# F387_Mini_Dev.net
KiCad netlist of a schematic drawn in EAGLE
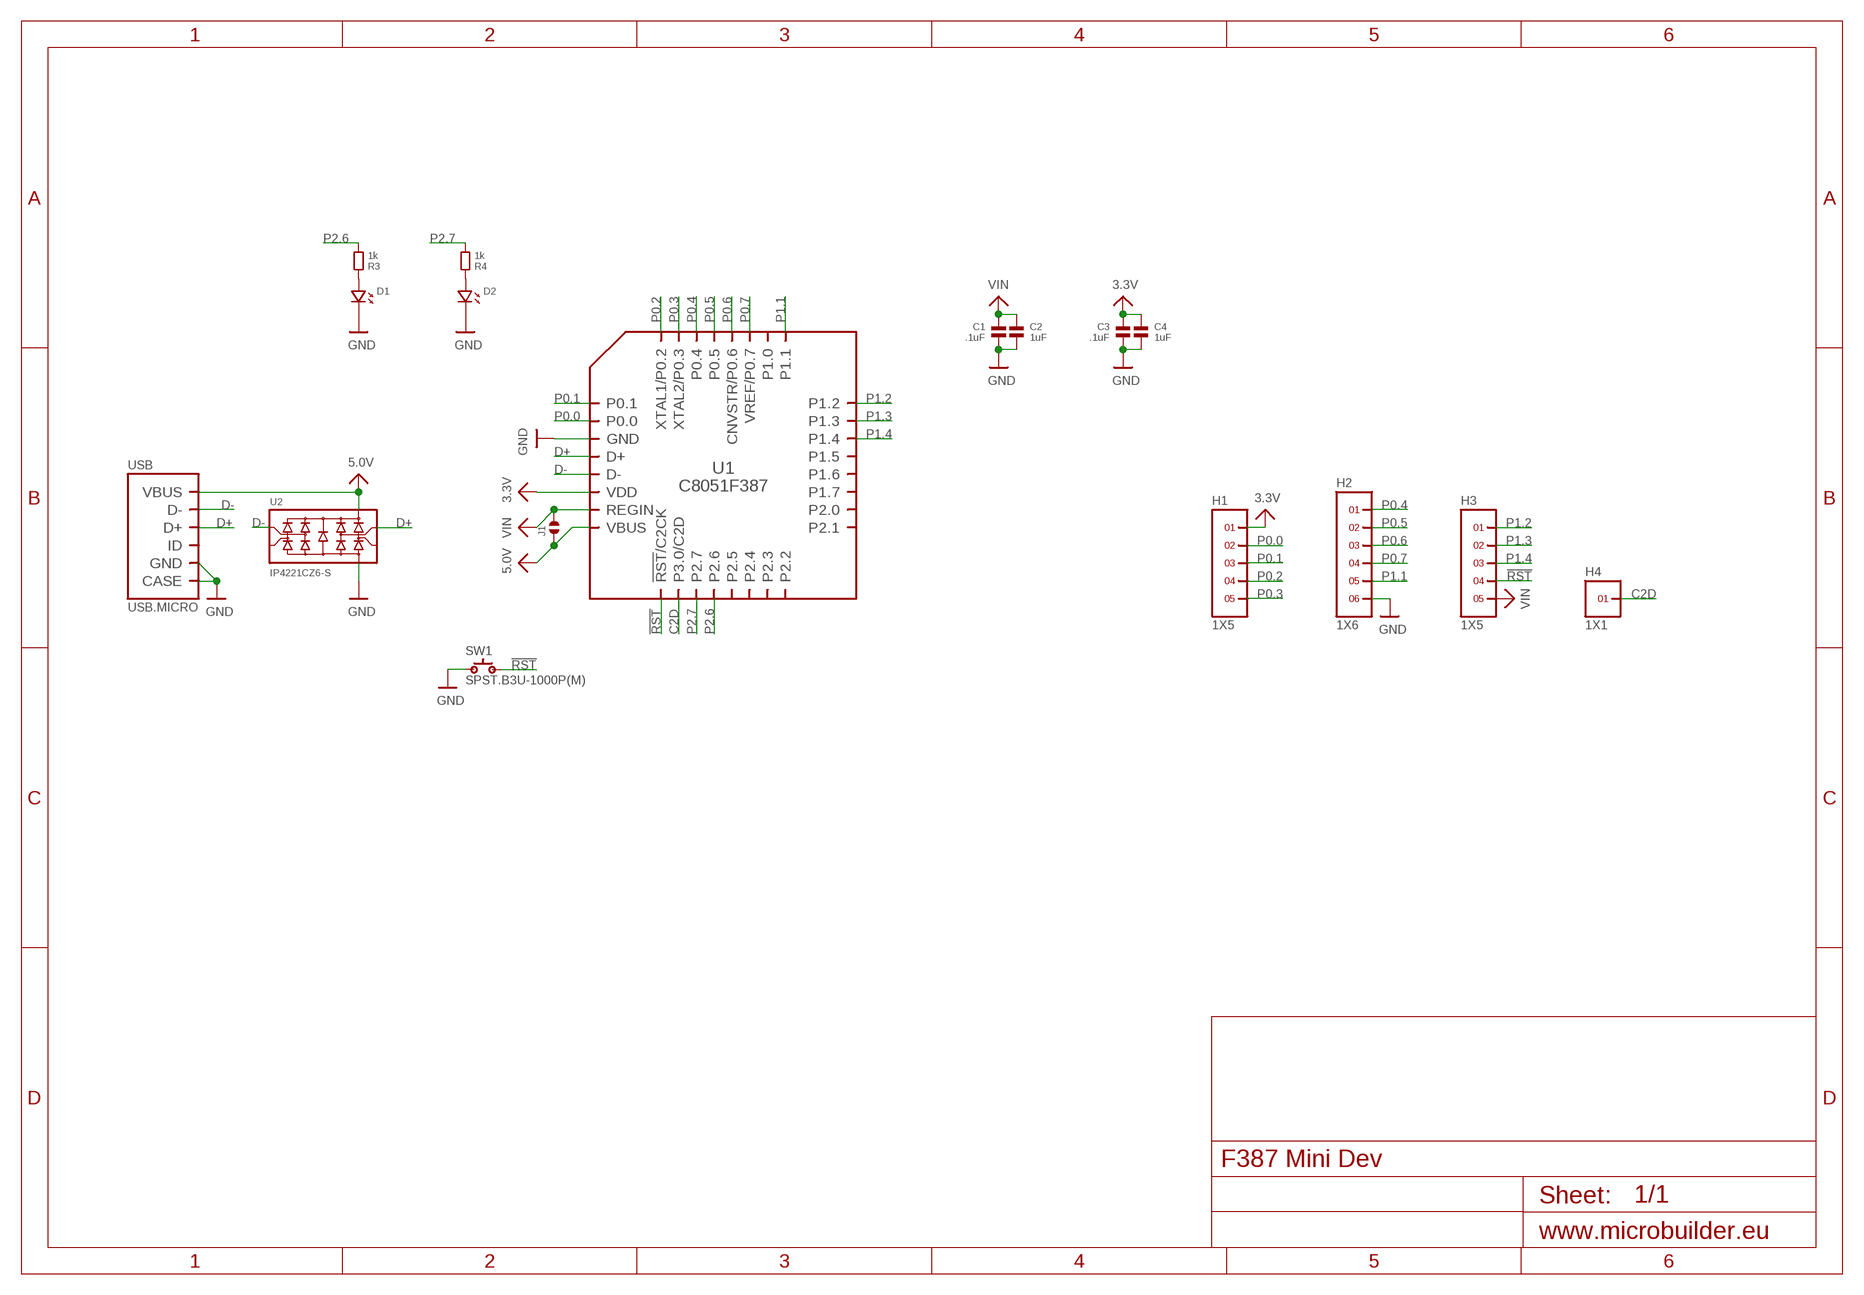
[diagram p0: schematic, sheet 1]

(export (version "E")
  (design (tool "Eeschema 10.0.6"))
  (components
    (comp (ref "C1")
      (value ".1uF")
      (footprint "eagle-import:0402")
      (libsource (lib "eagle-import") (part "CAPACITOR.0402"))
    )
    (comp (ref "C2")
      (value "1uF")
      (footprint "eagle-import:0402")
      (libsource (lib "eagle-import") (part "CAPACITOR.0402"))
    )
    (comp (ref "C3")
      (value ".1uF")
      (footprint "eagle-import:0402")
      (libsource (lib "eagle-import") (part "CAPACITOR.0402"))
    )
    (comp (ref "C4")
      (value "1uF")
      (footprint "eagle-import:0402")
      (libsource (lib "eagle-import") (part "CAPACITOR.0402"))
    )
    (comp (ref "D1")
      (value "LED.0402")
      (footprint "eagle-import:0402.LED")
      (libsource (lib "eagle-import") (part "LED.0402"))
    )
    (comp (ref "D2")
      (value "LED.0402")
      (footprint "eagle-import:0402.LED")
      (libsource (lib "eagle-import") (part "LED.0402"))
    )
    (comp (ref "H1")
      (value "1X5")
      (footprint "eagle-import:1X5")
      (libsource (lib "eagle-import") (part "1X5"))
    )
    (comp (ref "H2")
      (value "1X6")
      (footprint "eagle-import:1X6")
      (libsource (lib "eagle-import") (part "1X6"))
    )
    (comp (ref "H3")
      (value "1X5")
      (footprint "eagle-import:1X5")
      (libsource (lib "eagle-import") (part "1X5"))
    )
    (comp (ref "H4")
      (value "1X1")
      (footprint "eagle-import:1X1")
      (libsource (lib "eagle-import") (part "1X1"))
    )
    (comp (ref "J1")
      (value "SOLDERJUMPER.2.SML")
      (footprint "eagle-import:2.SML")
      (libsource (lib "eagle-import") (part "SOLDERJUMPER.2.SML"))
    )
    (comp (ref "R3")
      (value "1k")
      (footprint "eagle-import:0402")
      (libsource (lib "eagle-import") (part "RESISTOR.0402"))
    )
    (comp (ref "R4")
      (value "1k")
      (footprint "eagle-import:0402")
      (libsource (lib "eagle-import") (part "RESISTOR.0402"))
    )
    (comp (ref "SW1")
      (value "SPST.B3U-1000P(M)")
      (footprint "eagle-import:B3U-1000P(M)")
      (libsource (lib "eagle-import") (part "SPST.B3U-1000P(M)"))
    )
    (comp (ref "U1")
      (value "C8051F387")
      (footprint "eagle-import:QFN32")
      (libsource (lib "eagle-import") (part "C8051F381/3/5/7.QFN"))
    )
    (comp (ref "U2")
      (value "IP4221CZ6-S")
      (footprint "eagle-import:DFN1410-6")
      (libsource (lib "eagle-import") (part "IP4221CZ6-S"))
    )
    (comp (ref "USB")
      (value "USB.MICRO")
      (footprint "eagle-import:1554266-1")
      (libsource (lib "eagle-import") (part "USB.MICRO"))
    )
  )
  (nets
    (net (code "1") (name "/C2D") (class "Default")
      (node (ref "H4") (pin "1") (pinfunction "1_1") (pintype "bidirectional"))
      (node (ref "U1") (pin "10") (pinfunction "P3.0/C2D_10") (pintype "bidirectional"))
    )
    (net (code "2") (name "/D+") (class "Default")
      (node (ref "U1") (pin "4") (pinfunction "D+_4") (pintype "bidirectional"))
      (node (ref "U2") (pin "3") (pinfunction "3_3") (pintype "bidirectional"))
      (node (ref "USB") (pin "3") (pinfunction "D+_3") (pintype "bidirectional"))
    )
    (net (code "3") (name "/D-") (class "Default")
      (node (ref "U1") (pin "5") (pinfunction "D-_5") (pintype "bidirectional"))
      (node (ref "U2") (pin "1") (pinfunction "1_1") (pintype "bidirectional"))
      (node (ref "USB") (pin "2") (pinfunction "D-_2") (pintype "bidirectional"))
    )
    (net (code "4") (name "/P0.0") (class "Default")
      (node (ref "H1") (pin "2") (pinfunction "2_2") (pintype "bidirectional"))
      (node (ref "U1") (pin "2") (pinfunction "P0.0_2") (pintype "bidirectional"))
    )
    (net (code "5") (name "/P0.1") (class "Default")
      (node (ref "H1") (pin "3") (pinfunction "3_3") (pintype "bidirectional"))
      (node (ref "U1") (pin "1") (pinfunction "P0.1_1") (pintype "bidirectional"))
    )
    (net (code "6") (name "/P0.2") (class "Default")
      (node (ref "H1") (pin "4") (pinfunction "4_4") (pintype "bidirectional"))
      (node (ref "U1") (pin "32") (pinfunction "XTAL1/P0.2_32") (pintype "bidirectional"))
    )
    (net (code "7") (name "/P0.3") (class "Default")
      (node (ref "H1") (pin "5") (pinfunction "5_5") (pintype "bidirectional"))
      (node (ref "U1") (pin "31") (pinfunction "XTAL2/P0.3_31") (pintype "bidirectional"))
    )
    (net (code "8") (name "/P0.4") (class "Default")
      (node (ref "H2") (pin "1") (pinfunction "1_1") (pintype "bidirectional"))
      (node (ref "U1") (pin "30") (pinfunction "P0.4_30") (pintype "bidirectional"))
    )
    (net (code "9") (name "/P0.5") (class "Default")
      (node (ref "H2") (pin "2") (pinfunction "2_2") (pintype "bidirectional"))
      (node (ref "U1") (pin "29") (pinfunction "P0.5_29") (pintype "bidirectional"))
    )
    (net (code "10") (name "/P0.6") (class "Default")
      (node (ref "H2") (pin "3") (pinfunction "3_3") (pintype "bidirectional"))
      (node (ref "U1") (pin "28") (pinfunction "CNVSTR/P0.6_28") (pintype "bidirectional"))
    )
    (net (code "11") (name "/P0.7") (class "Default")
      (node (ref "H2") (pin "4") (pinfunction "4_4") (pintype "bidirectional"))
      (node (ref "U1") (pin "27") (pinfunction "VREF/P0.7_27") (pintype "bidirectional"))
    )
    (net (code "12") (name "/P1.1") (class "Default")
      (node (ref "H2") (pin "5") (pinfunction "5_5") (pintype "bidirectional"))
      (node (ref "U1") (pin "25") (pinfunction "P1.1_25") (pintype "bidirectional"))
    )
    (net (code "13") (name "/P1.2") (class "Default")
      (node (ref "H3") (pin "1") (pinfunction "1_1") (pintype "bidirectional"))
      (node (ref "U1") (pin "24") (pinfunction "P1.2_24") (pintype "bidirectional"))
    )
    (net (code "14") (name "/P1.3") (class "Default")
      (node (ref "H3") (pin "2") (pinfunction "2_2") (pintype "bidirectional"))
      (node (ref "U1") (pin "23") (pinfunction "P1.3_23") (pintype "bidirectional"))
    )
    (net (code "15") (name "/P1.4") (class "Default")
      (node (ref "H3") (pin "3") (pinfunction "3_3") (pintype "bidirectional"))
      (node (ref "U1") (pin "22") (pinfunction "P1.4_22") (pintype "bidirectional"))
    )
    (net (code "16") (name "/P2.6") (class "Default")
      (node (ref "R3") (pin "2") (pinfunction "2_2") (pintype "bidirectional"))
      (node (ref "U1") (pin "12") (pinfunction "P2.6_12") (pintype "bidirectional"))
    )
    (net (code "17") (name "/P2.7") (class "Default")
      (node (ref "R4") (pin "2") (pinfunction "2_2") (pintype "bidirectional"))
      (node (ref "U1") (pin "11") (pinfunction "P2.7_11") (pintype "bidirectional"))
    )
    (net (code "18") (name "/~{RST}") (class "Default")
      (node (ref "H3") (pin "4") (pinfunction "4_4") (pintype "bidirectional"))
      (node (ref "SW1") (pin "2") (pinfunction "2_2") (pintype "bidirectional"))
      (node (ref "U1") (pin "9") (pinfunction "~{RST}/C2CK_9") (pintype "bidirectional"))
    )
    (net (code "19") (name "3.3V") (class "Default")
      (node (ref "C3") (pin "1") (pinfunction "1_1") (pintype "bidirectional"))
      (node (ref "C4") (pin "1") (pinfunction "1_1") (pintype "bidirectional"))
      (node (ref "H1") (pin "1") (pinfunction "1_1") (pintype "bidirectional"))
      (node (ref "U1") (pin "6") (pinfunction "VDD_6") (pintype "bidirectional"))
    )
    (net (code "20") (name "5.0V") (class "Default")
      (node (ref "J1") (pin "1") (pinfunction "1_1") (pintype "bidirectional"))
      (node (ref "U1") (pin "8") (pinfunction "VBUS_8") (pintype "bidirectional"))
      (node (ref "U2") (pin "5") (pinfunction "5_5") (pintype "bidirectional"))
      (node (ref "USB") (pin "1") (pinfunction "VBUS_1") (pintype "bidirectional"))
    )
    (net (code "21") (name "GND") (class "Default")
      (node (ref "C1") (pin "2") (pinfunction "2_2") (pintype "bidirectional"))
      (node (ref "C2") (pin "2") (pinfunction "2_2") (pintype "bidirectional"))
      (node (ref "C3") (pin "2") (pinfunction "2_2") (pintype "bidirectional"))
      (node (ref "C4") (pin "2") (pinfunction "2_2") (pintype "bidirectional"))
      (node (ref "D1") (pin "P$2") (pinfunction "2_P$2") (pintype "bidirectional"))
      (node (ref "D2") (pin "P$2") (pinfunction "2_P$2") (pintype "bidirectional"))
      (node (ref "H2") (pin "6") (pinfunction "6_6") (pintype "bidirectional"))
      (node (ref "SW1") (pin "1") (pinfunction "1_1") (pintype "bidirectional"))
      (node (ref "U1") (pin "3") (pinfunction "GND_3") (pintype "bidirectional"))
      (node (ref "U1") (pin "PAD") (pinfunction "GND_PAD") (pintype "bidirectional"))
      (node (ref "U2") (pin "2") (pinfunction "2_2") (pintype "bidirectional"))
      (node (ref "USB") (pin "5") (pinfunction "GND_5") (pintype "bidirectional"))
      (node (ref "USB") (pin "PAD1@1") (pinfunction "CASE_PAD1@1") (pintype "bidirectional"))
      (node (ref "USB") (pin "PAD1@2") (pinfunction "CASE_PAD1@2") (pintype "bidirectional"))
      (node (ref "USB") (pin "PAD1@VIA1") (pinfunction "CASE_PAD1@VIA1") (pintype "bidirectional"))
      (node (ref "USB") (pin "PAD1@VIA2") (pinfunction "CASE_PAD1@VIA2") (pintype "bidirectional"))
      (node (ref "USB") (pin "PAD1@VIA3") (pinfunction "CASE_PAD1@VIA3") (pintype "bidirectional"))
      (node (ref "USB") (pin "PAD1@VIA4") (pinfunction "CASE_PAD1@VIA4") (pintype "bidirectional"))
      (node (ref "USB") (pin "PAD1@VIA5") (pinfunction "CASE_PAD1@VIA5") (pintype "bidirectional"))
      (node (ref "USB") (pin "PAD2") (pinfunction "CASE_PAD2") (pintype "bidirectional"))
      (node (ref "USB") (pin "PAD2@VIA1") (pinfunction "CASE_PAD2@VIA1") (pintype "bidirectional"))
      (node (ref "USB") (pin "PAD2@VIA2") (pinfunction "CASE_PAD2@VIA2") (pintype "bidirectional"))
      (node (ref "USB") (pin "PAD2@VIA3") (pinfunction "CASE_PAD2@VIA3") (pintype "bidirectional"))
      (node (ref "USB") (pin "PAD2@VIA4") (pinfunction "CASE_PAD2@VIA4") (pintype "bidirectional"))
      (node (ref "USB") (pin "PAD2@VIA5") (pinfunction "CASE_PAD2@VIA5") (pintype "bidirectional"))
      (node (ref "USB") (pin "PAD2@VIA6") (pinfunction "CASE_PAD2@VIA6") (pintype "bidirectional"))
      (node (ref "USB") (pin "PAD2@VIA7") (pinfunction "CASE_PAD2@VIA7") (pintype "bidirectional"))
      (node (ref "USB") (pin "PAD3") (pinfunction "CASE_PAD3") (pintype "bidirectional"))
      (node (ref "USB") (pin "PAD3@VIA1") (pinfunction "CASE_PAD3@VIA1") (pintype "bidirectional"))
      (node (ref "USB") (pin "PAD3@VIA2") (pinfunction "CASE_PAD3@VIA2") (pintype "bidirectional"))
      (node (ref "USB") (pin "PAD3@VIA3") (pinfunction "CASE_PAD3@VIA3") (pintype "bidirectional"))
      (node (ref "USB") (pin "PAD3@VIA4") (pinfunction "CASE_PAD3@VIA4") (pintype "bidirectional"))
      (node (ref "USB") (pin "PAD3@VIA5") (pinfunction "CASE_PAD3@VIA5") (pintype "bidirectional"))
      (node (ref "USB") (pin "PAD3@VIA6") (pinfunction "CASE_PAD3@VIA6") (pintype "bidirectional"))
      (node (ref "USB") (pin "PAD3@VIA7") (pinfunction "CASE_PAD3@VIA7") (pintype "bidirectional"))
      (node (ref "USB") (pin "PAD4@1") (pinfunction "CASE_PAD4@1") (pintype "bidirectional"))
      (node (ref "USB") (pin "PAD4@2") (pinfunction "CASE_PAD4@2") (pintype "bidirectional"))
      (node (ref "USB") (pin "PAD4@VIA1") (pinfunction "CASE_PAD4@VIA1") (pintype "bidirectional"))
      (node (ref "USB") (pin "PAD4@VIA2") (pinfunction "CASE_PAD4@VIA2") (pintype "bidirectional"))
      (node (ref "USB") (pin "PAD4@VIA3") (pinfunction "CASE_PAD4@VIA3") (pintype "bidirectional"))
      (node (ref "USB") (pin "PAD4@VIA4") (pinfunction "CASE_PAD4@VIA4") (pintype "bidirectional"))
      (node (ref "USB") (pin "PAD4@VIA5") (pinfunction "CASE_PAD4@VIA5") (pintype "bidirectional"))
    )
    (net (code "22") (name "Net-(D1-1)") (class "Default")
      (node (ref "D1") (pin "P$1") (pinfunction "1_P$1") (pintype "bidirectional"))
      (node (ref "R3") (pin "1") (pinfunction "1_1") (pintype "bidirectional"))
    )
    (net (code "23") (name "Net-(D2-1)") (class "Default")
      (node (ref "D2") (pin "P$1") (pinfunction "1_P$1") (pintype "bidirectional"))
      (node (ref "R4") (pin "1") (pinfunction "1_1") (pintype "bidirectional"))
    )
    (net (code "24") (name "VIN") (class "Default")
      (node (ref "C1") (pin "1") (pinfunction "1_1") (pintype "bidirectional"))
      (node (ref "C2") (pin "1") (pinfunction "1_1") (pintype "bidirectional"))
      (node (ref "H3") (pin "5") (pinfunction "5_5") (pintype "bidirectional"))
      (node (ref "J1") (pin "2") (pinfunction "2_2") (pintype "bidirectional"))
      (node (ref "U1") (pin "7") (pinfunction "REGIN_7") (pintype "bidirectional"))
    )
    (net (code "25") (name "unconnected-(U1-P1.0-Pad26)") (class "Default")
      (node (ref "U1") (pin "26") (pinfunction "P1.0_26") (pintype "bidirectional"))
    )
    (net (code "26") (name "unconnected-(U1-P1.5-Pad21)") (class "Default")
      (node (ref "U1") (pin "21") (pinfunction "P1.5_21") (pintype "bidirectional"))
    )
    (net (code "27") (name "unconnected-(U1-P1.6-Pad20)") (class "Default")
      (node (ref "U1") (pin "20") (pinfunction "P1.6_20") (pintype "bidirectional"))
    )
    (net (code "28") (name "unconnected-(U1-P1.7-Pad19)") (class "Default")
      (node (ref "U1") (pin "19") (pinfunction "P1.7_19") (pintype "bidirectional"))
    )
    (net (code "29") (name "unconnected-(U1-P2.0-Pad18)") (class "Default")
      (node (ref "U1") (pin "18") (pinfunction "P2.0_18") (pintype "bidirectional"))
    )
    (net (code "30") (name "unconnected-(U1-P2.1-Pad17)") (class "Default")
      (node (ref "U1") (pin "17") (pinfunction "P2.1_17") (pintype "bidirectional"))
    )
    (net (code "31") (name "unconnected-(U1-P2.2-Pad16)") (class "Default")
      (node (ref "U1") (pin "16") (pinfunction "P2.2_16") (pintype "bidirectional"))
    )
    (net (code "32") (name "unconnected-(U1-P2.3-Pad15)") (class "Default")
      (node (ref "U1") (pin "15") (pinfunction "P2.3_15") (pintype "bidirectional"))
    )
    (net (code "33") (name "unconnected-(U1-P2.4-Pad14)") (class "Default")
      (node (ref "U1") (pin "14") (pinfunction "P2.4_14") (pintype "bidirectional"))
    )
    (net (code "34") (name "unconnected-(U1-P2.5-Pad13)") (class "Default")
      (node (ref "U1") (pin "13") (pinfunction "P2.5_13") (pintype "bidirectional"))
    )
    (net (code "35") (name "unconnected-(U2-Pad4)") (class "Default")
      (node (ref "U2") (pin "4") (pinfunction "4_4") (pintype "bidirectional"))
    )
    (net (code "36") (name "unconnected-(U2-Pad6)") (class "Default")
      (node (ref "U2") (pin "6") (pinfunction "6_6") (pintype "bidirectional"))
    )
    (net (code "37") (name "unconnected-(USB-ID-Pad4)") (class "Default")
      (node (ref "USB") (pin "4") (pinfunction "ID_4") (pintype "bidirectional"))
    )
  )
)
